# arduino_uno_pcb__with_lcd.net
KiCad netlist of a schematic drawn in EAGLE
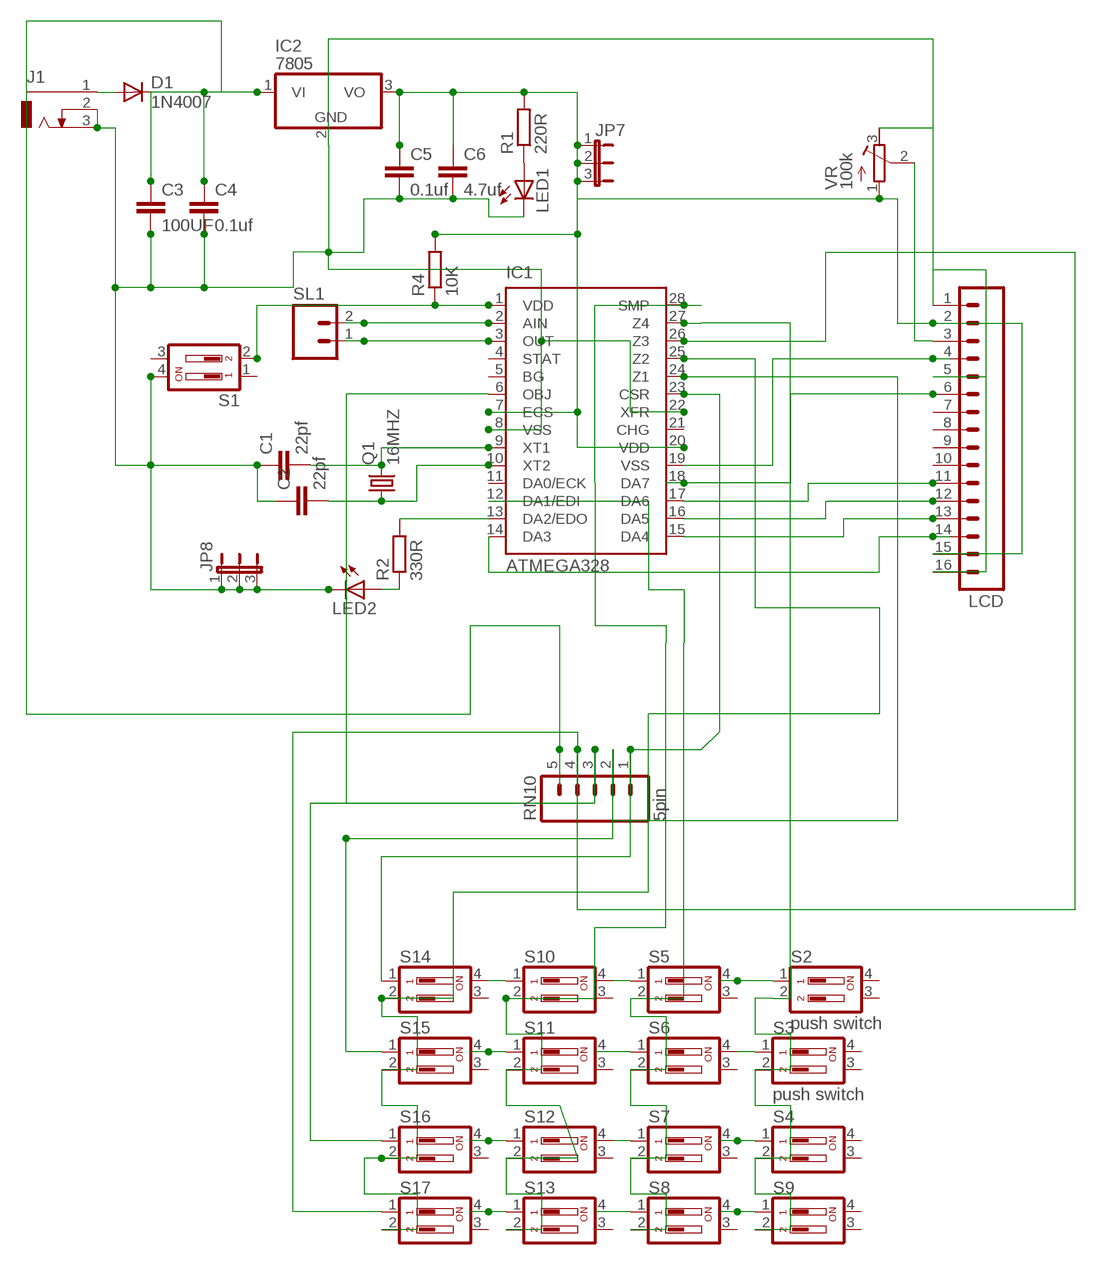
[diagram p0: schematic, sheet 1]

(export (version "E")
  (design (tool "Eeschema 10.0.6"))
  (components
    (comp (ref "C1")
      (value "22pf")
      (footprint "eagle-import:C2.5-2")
      (libsource (lib "eagle-import") (part "C2.5/2"))
    )
    (comp (ref "C2")
      (value "22pf")
      (footprint "eagle-import:C2.5-2")
      (libsource (lib "eagle-import") (part "C2.5/2"))
    )
    (comp (ref "C3")
      (value "100UF")
      (footprint "eagle-import:C2.5-2")
      (libsource (lib "eagle-import") (part "C2.5/2"))
    )
    (comp (ref "C4")
      (value "0.1uf")
      (footprint "eagle-import:C2.5-2")
      (libsource (lib "eagle-import") (part "C2.5/2"))
    )
    (comp (ref "C5")
      (value "0.1uf")
      (footprint "eagle-import:C2.5-2")
      (libsource (lib "eagle-import") (part "C2.5/2"))
    )
    (comp (ref "C6")
      (value "4.7uf")
      (footprint "eagle-import:C2.5-2")
      (libsource (lib "eagle-import") (part "C2.5/2"))
    )
    (comp (ref "D1")
      (value "1N4007")
      (footprint "eagle-import:DO41-10")
      (libsource (lib "eagle-import") (part "1N4004"))
    )
    (comp (ref "IC1")
      (value "ATMEGA328")
      (footprint "eagle-import:DIL28-3")
      (libsource (lib "eagle-import") (part "QT9701BD"))
    )
    (comp (ref "IC2")
      (value "7805")
      (footprint "eagle-import:TO220V")
      (libsource (lib "eagle-import") (part "78TV6"))
    )
    (comp (ref "J1")
      (value "DCJ0303")
      (footprint "eagle-import:DCJ0303")
      (libsource (lib "eagle-import") (part "DCJ0303"))
    )
    (comp (ref "JP7")
      (value "JP2E")
      (footprint "eagle-import:JP2")
      (libsource (lib "eagle-import") (part "JP2E"))
    )
    (comp (ref "JP8")
      (value "JP2E")
      (footprint "eagle-import:JP2")
      (libsource (lib "eagle-import") (part "JP2E"))
    )
    (comp (ref "LCD")
      (value "M16")
      (footprint "eagle-import:16P")
      (libsource (lib "eagle-import") (part "M16"))
    )
    (comp (ref "LED1")
      (value "LED3MM")
      (footprint "eagle-import:LED3MM")
      (libsource (lib "eagle-import") (part "LED3MM"))
    )
    (comp (ref "LED2")
      (value "LED3MM")
      (footprint "eagle-import:LED3MM")
      (libsource (lib "eagle-import") (part "LED3MM"))
    )
    (comp (ref "Q1")
      (value "16MHZ")
      (footprint "eagle-import:HC49_S")
      (libsource (lib "eagle-import") (part "CRYSTALHC49S"))
    )
    (comp (ref "R1")
      (value "220R")
      (footprint "eagle-import:0207_10")
      (libsource (lib "eagle-import") (part "R-EU_0207/10"))
    )
    (comp (ref "R2")
      (value "330R")
      (footprint "eagle-import:0207_10")
      (libsource (lib "eagle-import") (part "R-EU_0207/10"))
    )
    (comp (ref "R4")
      (value "10K")
      (footprint "eagle-import:0207_10")
      (libsource (lib "eagle-import") (part "R-EU_0207/10"))
    )
    (comp (ref "RN10")
      (value "5pin")
      (footprint "eagle-import:05P")
      (libsource (lib "eagle-import") (part "M05"))
    )
    (comp (ref "S1")
      (value "DP02")
      (footprint "eagle-import:DP-02")
      (fields (field (name "MPN") "MCDP02"))
      (libsource (lib "eagle-import") (part "DP02"))
    )
    (comp (ref "S2")
      (value "push switch")
      (footprint "eagle-import:DP-02")
      (fields (field (name "MPN") "MCDP02"))
      (libsource (lib "eagle-import") (part "DP02"))
    )
    (comp (ref "S3")
      (value "push switch")
      (footprint "eagle-import:DP-02")
      (fields (field (name "MPN") "MCDP02"))
      (libsource (lib "eagle-import") (part "DP02"))
    )
    (comp (ref "S4")
      (value "DP02")
      (footprint "eagle-import:DP-02")
      (fields (field (name "MPN") "MCDP02"))
      (libsource (lib "eagle-import") (part "DP02"))
    )
    (comp (ref "S5")
      (value "DP02")
      (footprint "eagle-import:DP-02")
      (fields (field (name "MPN") "MCDP02"))
      (libsource (lib "eagle-import") (part "DP02"))
    )
    (comp (ref "S6")
      (value "DP02")
      (footprint "eagle-import:DP-02")
      (fields (field (name "MPN") "MCDP02"))
      (libsource (lib "eagle-import") (part "DP02"))
    )
    (comp (ref "S7")
      (value "DP02")
      (footprint "eagle-import:DP-02")
      (fields (field (name "MPN") "MCDP02"))
      (libsource (lib "eagle-import") (part "DP02"))
    )
    (comp (ref "S8")
      (value "DP02")
      (footprint "eagle-import:DP-02")
      (fields (field (name "MPN") "MCDP02"))
      (libsource (lib "eagle-import") (part "DP02"))
    )
    (comp (ref "S9")
      (value "DP02")
      (footprint "eagle-import:DP-02")
      (fields (field (name "MPN") "MCDP02"))
      (libsource (lib "eagle-import") (part "DP02"))
    )
    (comp (ref "S10")
      (value "DP02")
      (footprint "eagle-import:DP-02")
      (fields (field (name "MPN") "MCDP02"))
      (libsource (lib "eagle-import") (part "DP02"))
    )
    (comp (ref "S11")
      (value "DP02")
      (footprint "eagle-import:DP-02")
      (fields (field (name "MPN") "MCDP02"))
      (libsource (lib "eagle-import") (part "DP02"))
    )
    (comp (ref "S12")
      (value "DP02")
      (footprint "eagle-import:DP-02")
      (fields (field (name "MPN") "MCDP02"))
      (libsource (lib "eagle-import") (part "DP02"))
    )
    (comp (ref "S13")
      (value "DP02")
      (footprint "eagle-import:DP-02")
      (fields (field (name "MPN") "MCDP02"))
      (libsource (lib "eagle-import") (part "DP02"))
    )
    (comp (ref "S14")
      (value "DP02")
      (footprint "eagle-import:DP-02")
      (fields (field (name "MPN") "MCDP02"))
      (libsource (lib "eagle-import") (part "DP02"))
    )
    (comp (ref "S15")
      (value "DP02")
      (footprint "eagle-import:DP-02")
      (fields (field (name "MPN") "MCDP02"))
      (libsource (lib "eagle-import") (part "DP02"))
    )
    (comp (ref "S16")
      (value "DP02")
      (footprint "eagle-import:DP-02")
      (fields (field (name "MPN") "MCDP02"))
      (libsource (lib "eagle-import") (part "DP02"))
    )
    (comp (ref "S17")
      (value "DP02")
      (footprint "eagle-import:DP-02")
      (fields (field (name "MPN") "MCDP02"))
      (libsource (lib "eagle-import") (part "DP02"))
    )
    (comp (ref "SL1")
      (value "M02")
      (footprint "eagle-import:02P")
      (libsource (lib "eagle-import") (part "M02"))
    )
    (comp (ref "VR")
      (value "100k")
      (footprint "eagle-import:RTRIM64P")
      (libsource (lib "eagle-import") (part "R-TRIMM64P"))
    )
  )
  (nets
    (net (code "1") (name "Net-(D1-PadA)") (class "Default")
      (node (ref "D1") (pin "A") (pinfunction "A_A") (pintype "passive"))
      (node (ref "J1") (pin "1") (pinfunction "1_1") (pintype "passive"))
    )
    (net (code "2") (name "Net-(IC1-AIN)") (class "Default")
      (node (ref "IC1") (pin "2") (pinfunction "AIN_2") (pintype "input"))
      (node (ref "SL1") (pin "2") (pinfunction "2_2") (pintype "passive"))
    )
    (net (code "3") (name "Net-(IC1-CSR)") (class "Default")
      (node (ref "IC1") (pin "23") (pinfunction "CSR_23") (pintype "output"))
      (node (ref "RN10") (pin "1") (pinfunction "1_1") (pintype "passive"))
      (node (ref "S14") (pin "1") (pinfunction "1_1") (pintype "passive"))
    )
    (net (code "4") (name "Net-(IC1-DA1{slash}EDI)") (class "Default")
      (node (ref "IC1") (pin "12") (pinfunction "DA1/EDI_12") (pintype "output"))
      (node (ref "S5") (pin "2") (pinfunction "2_2") (pintype "passive"))
      (node (ref "S6") (pin "2") (pinfunction "2_2") (pintype "passive"))
      (node (ref "S7") (pin "2") (pinfunction "2_2") (pintype "passive"))
      (node (ref "S8") (pin "2") (pinfunction "2_2") (pintype "passive"))
    )
    (net (code "5") (name "Net-(IC1-DA2{slash}EDO)") (class "Default")
      (node (ref "IC1") (pin "13") (pinfunction "DA2/EDO_13") (pintype "output"))
      (node (ref "R2") (pin "2") (pinfunction "2_2") (pintype "passive"))
    )
    (net (code "6") (name "Net-(IC1-DA3)") (class "Default")
      (node (ref "IC1") (pin "14") (pinfunction "DA3_14") (pintype "output"))
      (node (ref "LCD") (pin "14") (pinfunction "14_14") (pintype "passive"))
    )
    (net (code "7") (name "Net-(IC1-DA4)") (class "Default")
      (node (ref "IC1") (pin "15") (pinfunction "DA4_15") (pintype "output"))
      (node (ref "LCD") (pin "13") (pinfunction "13_13") (pintype "passive"))
    )
    (net (code "8") (name "Net-(IC1-DA5)") (class "Default")
      (node (ref "IC1") (pin "16") (pinfunction "DA5_16") (pintype "output"))
      (node (ref "LCD") (pin "12") (pinfunction "12_12") (pintype "passive"))
    )
    (net (code "9") (name "Net-(IC1-DA6)") (class "Default")
      (node (ref "IC1") (pin "17") (pinfunction "DA6_17") (pintype "output"))
      (node (ref "LCD") (pin "11") (pinfunction "11_11") (pintype "passive"))
    )
    (net (code "10") (name "Net-(IC1-DA7)") (class "Default")
      (node (ref "IC1") (pin "18") (pinfunction "DA7_18") (pintype "output"))
      (node (ref "LCD") (pin "6") (pinfunction "6_6") (pintype "passive"))
    )
    (net (code "11") (name "Net-(IC1-ECS)") (class "Default")
      (node (ref "C5") (pin "1") (pinfunction "1_1") (pintype "passive"))
      (node (ref "C6") (pin "1") (pinfunction "1_1") (pintype "passive"))
      (node (ref "IC1") (pin "20") (pinfunction "VDD_20") (pintype "input"))
      (node (ref "IC1") (pin "7") (pinfunction "ECS_7") (pintype "output"))
      (node (ref "IC2") (pin "3") (pinfunction "VO_3") (pintype "passive"))
      (node (ref "JP7") (pin "1") (pinfunction "1_1") (pintype "passive"))
      (node (ref "JP7") (pin "2") (pinfunction "2_2") (pintype "passive"))
      (node (ref "JP7") (pin "3") (pinfunction "3_3") (pintype "passive"))
      (node (ref "LCD") (pin "15") (pinfunction "15_15") (pintype "passive"))
      (node (ref "LCD") (pin "2") (pinfunction "2_2") (pintype "passive"))
      (node (ref "R1") (pin "2") (pinfunction "2_2") (pintype "passive"))
      (node (ref "R4") (pin "2") (pinfunction "2_2") (pintype "passive"))
      (node (ref "VR") (pin "1") (pinfunction "E_1") (pintype "passive"))
    )
    (net (code "12") (name "Net-(IC1-OBJ)") (class "Default")
      (node (ref "IC1") (pin "6") (pinfunction "OBJ_6") (pintype "input"))
      (node (ref "RN10") (pin "3") (pinfunction "3_3") (pintype "passive"))
      (node (ref "S16") (pin "1") (pinfunction "1_1") (pintype "passive"))
    )
    (net (code "13") (name "Net-(IC1-OUT)") (class "Default")
      (node (ref "IC1") (pin "3") (pinfunction "OUT_3") (pintype "output"))
      (node (ref "SL1") (pin "1") (pinfunction "1_1") (pintype "passive"))
    )
    (net (code "14") (name "Net-(IC1-SMP)") (class "Default")
      (node (ref "IC1") (pin "28") (pinfunction "SMP_28") (pintype "output"))
      (node (ref "S10") (pin "2") (pinfunction "2_2") (pintype "passive"))
      (node (ref "S11") (pin "2") (pinfunction "2_2") (pintype "passive"))
      (node (ref "S12") (pin "2") (pinfunction "2_2") (pintype "passive"))
      (node (ref "S13") (pin "2") (pinfunction "2_2") (pintype "passive"))
    )
    (net (code "15") (name "Net-(IC1-VDD-Pad1)") (class "Default")
      (node (ref "IC1") (pin "1") (pinfunction "VDD_1") (pintype "input"))
      (node (ref "R4") (pin "1") (pinfunction "1_1") (pintype "passive"))
      (node (ref "S1") (pin "2") (pinfunction "2_2") (pintype "passive"))
    )
    (net (code "16") (name "Net-(IC1-VSS-Pad19)") (class "Default")
      (node (ref "IC1") (pin "19") (pinfunction "VSS_19") (pintype "input"))
      (node (ref "LCD") (pin "4") (pinfunction "4_4") (pintype "passive"))
    )
    (net (code "17") (name "Net-(IC1-XFR)") (class "Default")
      (node (ref "C1") (pin "1") (pinfunction "1_1") (pintype "passive"))
      (node (ref "C2") (pin "1") (pinfunction "1_1") (pintype "passive"))
      (node (ref "C3") (pin "2") (pinfunction "2_2") (pintype "passive"))
      (node (ref "C4") (pin "2") (pinfunction "2_2") (pintype "passive"))
      (node (ref "C5") (pin "2") (pinfunction "2_2") (pintype "passive"))
      (node (ref "C6") (pin "2") (pinfunction "2_2") (pintype "passive"))
      (node (ref "IC1") (pin "22") (pinfunction "XFR_22") (pintype "output"))
      (node (ref "IC1") (pin "8") (pinfunction "VSS_8") (pintype "input"))
      (node (ref "IC2") (pin "2") (pinfunction "GND_2") (pintype "passive"))
      (node (ref "J1") (pin "2") (pinfunction "2_2") (pintype "passive"))
      (node (ref "J1") (pin "3") (pinfunction "3_3") (pintype "passive"))
      (node (ref "JP8") (pin "1") (pinfunction "1_1") (pintype "passive"))
      (node (ref "JP8") (pin "2") (pinfunction "2_2") (pintype "passive"))
      (node (ref "JP8") (pin "3") (pinfunction "3_3") (pintype "passive"))
      (node (ref "LCD") (pin "1") (pinfunction "1_1") (pintype "passive"))
      (node (ref "LCD") (pin "16") (pinfunction "16_16") (pintype "passive"))
      (node (ref "LCD") (pin "5") (pinfunction "5_5") (pintype "passive"))
      (node (ref "LED1") (pin "K") (pinfunction "C_K") (pintype "passive"))
      (node (ref "LED2") (pin "K") (pinfunction "C_K") (pintype "passive"))
      (node (ref "S1") (pin "4") (pinfunction "4_4") (pintype "passive"))
      (node (ref "VR") (pin "3") (pinfunction "A_3") (pintype "passive"))
    )
    (net (code "18") (name "Net-(IC1-XT1)") (class "Default")
      (node (ref "C1") (pin "2") (pinfunction "2_2") (pintype "passive"))
      (node (ref "IC1") (pin "9") (pinfunction "XT1_9") (pintype "input"))
      (node (ref "Q1") (pin "2") (pinfunction "2_2") (pintype "passive"))
    )
    (net (code "19") (name "Net-(IC1-XT2)") (class "Default")
      (node (ref "C2") (pin "2") (pinfunction "2_2") (pintype "passive"))
      (node (ref "IC1") (pin "10") (pinfunction "XT2_10") (pintype "output"))
      (node (ref "Q1") (pin "1") (pinfunction "1_1") (pintype "passive"))
    )
    (net (code "20") (name "Net-(IC1-Z1)") (class "Default")
      (node (ref "IC1") (pin "24") (pinfunction "Z1_24") (pintype "output"))
      (node (ref "RN10") (pin "2") (pinfunction "2_2") (pintype "passive"))
      (node (ref "S15") (pin "1") (pinfunction "1_1") (pintype "passive"))
    )
    (net (code "21") (name "Net-(IC1-Z2)") (class "Default")
      (node (ref "IC1") (pin "25") (pinfunction "Z2_25") (pintype "output"))
      (node (ref "S14") (pin "2") (pinfunction "2_2") (pintype "passive"))
      (node (ref "S15") (pin "2") (pinfunction "2_2") (pintype "passive"))
      (node (ref "S16") (pin "2") (pinfunction "2_2") (pintype "passive"))
      (node (ref "S17") (pin "2") (pinfunction "2_2") (pintype "passive"))
    )
    (net (code "22") (name "Net-(IC1-Z3)") (class "Default")
      (node (ref "IC1") (pin "26") (pinfunction "Z3_26") (pintype "output"))
      (node (ref "RN10") (pin "4") (pinfunction "4_4") (pintype "passive"))
      (node (ref "S17") (pin "1") (pinfunction "1_1") (pintype "passive"))
    )
    (net (code "23") (name "Net-(IC1-Z4)") (class "Default")
      (node (ref "IC1") (pin "27") (pinfunction "Z4_27") (pintype "output"))
      (node (ref "S2") (pin "2") (pinfunction "2_2") (pintype "passive"))
      (node (ref "S3") (pin "2") (pinfunction "2_2") (pintype "passive"))
      (node (ref "S4") (pin "2") (pinfunction "2_2") (pintype "passive"))
      (node (ref "S9") (pin "2") (pinfunction "2_2") (pintype "passive"))
    )
    (net (code "24") (name "Net-(IC2-VI)") (class "Default")
      (node (ref "C3") (pin "1") (pinfunction "1_1") (pintype "passive"))
      (node (ref "C4") (pin "1") (pinfunction "1_1") (pintype "passive"))
      (node (ref "D1") (pin "C") (pinfunction "C_C") (pintype "passive"))
      (node (ref "IC2") (pin "1") (pinfunction "VI_1") (pintype "input"))
      (node (ref "RN10") (pin "5") (pinfunction "5_5") (pintype "passive"))
    )
    (net (code "25") (name "Net-(LED1-PadA)") (class "Default")
      (node (ref "LED1") (pin "A") (pinfunction "A_A") (pintype "passive"))
      (node (ref "R1") (pin "1") (pinfunction "1_1") (pintype "passive"))
    )
    (net (code "26") (name "Net-(LED2-PadA)") (class "Default")
      (node (ref "LED2") (pin "A") (pinfunction "A_A") (pintype "passive"))
      (node (ref "R2") (pin "1") (pinfunction "1_1") (pintype "passive"))
    )
    (net (code "27") (name "Net-(S2-Pad1)") (class "Default")
      (node (ref "S2") (pin "1") (pinfunction "1_1") (pintype "passive"))
      (node (ref "S5") (pin "4") (pinfunction "4_4") (pintype "passive"))
    )
    (net (code "28") (name "Net-(S3-Pad1)") (class "Default")
      (node (ref "S3") (pin "1") (pinfunction "1_1") (pintype "passive"))
      (node (ref "S6") (pin "4") (pinfunction "4_4") (pintype "passive"))
    )
    (net (code "29") (name "Net-(S4-Pad1)") (class "Default")
      (node (ref "S4") (pin "1") (pinfunction "1_1") (pintype "passive"))
      (node (ref "S7") (pin "4") (pinfunction "4_4") (pintype "passive"))
    )
    (net (code "30") (name "Net-(S8-Pad4)") (class "Default")
      (node (ref "S8") (pin "4") (pinfunction "4_4") (pintype "passive"))
      (node (ref "S9") (pin "1") (pinfunction "1_1") (pintype "passive"))
    )
    (net (code "31") (name "Net-(S10-Pad1)") (class "Default")
      (node (ref "S10") (pin "1") (pinfunction "1_1") (pintype "passive"))
      (node (ref "S14") (pin "4") (pinfunction "4_4") (pintype "passive"))
    )
    (net (code "32") (name "Net-(S10-Pad4)") (class "Default")
      (node (ref "S10") (pin "4") (pinfunction "4_4") (pintype "passive"))
      (node (ref "S5") (pin "1") (pinfunction "1_1") (pintype "passive"))
    )
    (net (code "33") (name "Net-(S11-Pad1)") (class "Default")
      (node (ref "S11") (pin "1") (pinfunction "1_1") (pintype "passive"))
      (node (ref "S15") (pin "4") (pinfunction "4_4") (pintype "passive"))
    )
    (net (code "34") (name "Net-(S11-Pad4)") (class "Default")
      (node (ref "S11") (pin "4") (pinfunction "4_4") (pintype "passive"))
      (node (ref "S6") (pin "1") (pinfunction "1_1") (pintype "passive"))
    )
    (net (code "35") (name "Net-(S12-Pad1)") (class "Default")
      (node (ref "S12") (pin "1") (pinfunction "1_1") (pintype "passive"))
      (node (ref "S16") (pin "4") (pinfunction "4_4") (pintype "passive"))
    )
    (net (code "36") (name "Net-(S12-Pad4)") (class "Default")
      (node (ref "S12") (pin "4") (pinfunction "4_4") (pintype "passive"))
      (node (ref "S7") (pin "1") (pinfunction "1_1") (pintype "passive"))
    )
    (net (code "37") (name "Net-(S13-Pad1)") (class "Default")
      (node (ref "S13") (pin "1") (pinfunction "1_1") (pintype "passive"))
      (node (ref "S17") (pin "4") (pinfunction "4_4") (pintype "passive"))
    )
    (net (code "38") (name "Net-(S13-Pad4)") (class "Default")
      (node (ref "S13") (pin "4") (pinfunction "4_4") (pintype "passive"))
      (node (ref "S8") (pin "1") (pinfunction "1_1") (pintype "passive"))
    )
    (net (code "39") (name "Net-(VR-S)") (class "Default")
      (node (ref "LCD") (pin "3") (pinfunction "3_3") (pintype "passive"))
      (node (ref "VR") (pin "2") (pinfunction "S_2") (pintype "passive"))
    )
    (net (code "40") (name "unconnected-(IC1-BG-Pad5)") (class "Default")
      (node (ref "IC1") (pin "5") (pinfunction "BG_5") (pintype "input"))
    )
    (net (code "41") (name "unconnected-(IC1-CHG-Pad21)") (class "Default")
      (node (ref "IC1") (pin "21") (pinfunction "CHG_21") (pintype "output"))
    )
    (net (code "42") (name "unconnected-(IC1-DA0{slash}ECK-Pad11)") (class "Default")
      (node (ref "IC1") (pin "11") (pinfunction "DA0/ECK_11") (pintype "output"))
    )
    (net (code "43") (name "unconnected-(IC1-STAT-Pad4)") (class "Default")
      (node (ref "IC1") (pin "4") (pinfunction "STAT_4") (pintype "output"))
    )
    (net (code "44") (name "unconnected-(LCD-Pad7)") (class "Default")
      (node (ref "LCD") (pin "7") (pinfunction "7_7") (pintype "passive"))
    )
    (net (code "45") (name "unconnected-(LCD-Pad8)") (class "Default")
      (node (ref "LCD") (pin "8") (pinfunction "8_8") (pintype "passive"))
    )
    (net (code "46") (name "unconnected-(LCD-Pad9)") (class "Default")
      (node (ref "LCD") (pin "9") (pinfunction "9_9") (pintype "passive"))
    )
    (net (code "47") (name "unconnected-(LCD-Pad10)") (class "Default")
      (node (ref "LCD") (pin "10") (pinfunction "10_10") (pintype "passive"))
    )
    (net (code "48") (name "unconnected-(S1-Pad1)") (class "Default")
      (node (ref "S1") (pin "1") (pinfunction "1_1") (pintype "passive"))
    )
    (net (code "49") (name "unconnected-(S1-Pad3)") (class "Default")
      (node (ref "S1") (pin "3") (pinfunction "3_3") (pintype "passive"))
    )
    (net (code "50") (name "unconnected-(S2-Pad3)") (class "Default")
      (node (ref "S2") (pin "3") (pinfunction "3_3") (pintype "passive"))
    )
    (net (code "51") (name "unconnected-(S2-Pad4)") (class "Default")
      (node (ref "S2") (pin "4") (pinfunction "4_4") (pintype "passive"))
    )
    (net (code "52") (name "unconnected-(S3-Pad3)") (class "Default")
      (node (ref "S3") (pin "3") (pinfunction "3_3") (pintype "passive"))
    )
    (net (code "53") (name "unconnected-(S3-Pad4)") (class "Default")
      (node (ref "S3") (pin "4") (pinfunction "4_4") (pintype "passive"))
    )
    (net (code "54") (name "unconnected-(S4-Pad3)") (class "Default")
      (node (ref "S4") (pin "3") (pinfunction "3_3") (pintype "passive"))
    )
    (net (code "55") (name "unconnected-(S4-Pad4)") (class "Default")
      (node (ref "S4") (pin "4") (pinfunction "4_4") (pintype "passive"))
    )
    (net (code "56") (name "unconnected-(S5-Pad3)") (class "Default")
      (node (ref "S5") (pin "3") (pinfunction "3_3") (pintype "passive"))
    )
    (net (code "57") (name "unconnected-(S6-Pad3)") (class "Default")
      (node (ref "S6") (pin "3") (pinfunction "3_3") (pintype "passive"))
    )
    (net (code "58") (name "unconnected-(S7-Pad3)") (class "Default")
      (node (ref "S7") (pin "3") (pinfunction "3_3") (pintype "passive"))
    )
    (net (code "59") (name "unconnected-(S8-Pad3)") (class "Default")
      (node (ref "S8") (pin "3") (pinfunction "3_3") (pintype "passive"))
    )
    (net (code "60") (name "unconnected-(S9-Pad3)") (class "Default")
      (node (ref "S9") (pin "3") (pinfunction "3_3") (pintype "passive"))
    )
    (net (code "61") (name "unconnected-(S9-Pad4)") (class "Default")
      (node (ref "S9") (pin "4") (pinfunction "4_4") (pintype "passive"))
    )
    (net (code "62") (name "unconnected-(S10-Pad3)") (class "Default")
      (node (ref "S10") (pin "3") (pinfunction "3_3") (pintype "passive"))
    )
    (net (code "63") (name "unconnected-(S11-Pad3)") (class "Default")
      (node (ref "S11") (pin "3") (pinfunction "3_3") (pintype "passive"))
    )
    (net (code "64") (name "unconnected-(S12-Pad3)") (class "Default")
      (node (ref "S12") (pin "3") (pinfunction "3_3") (pintype "passive"))
    )
    (net (code "65") (name "unconnected-(S13-Pad3)") (class "Default")
      (node (ref "S13") (pin "3") (pinfunction "3_3") (pintype "passive"))
    )
    (net (code "66") (name "unconnected-(S14-Pad3)") (class "Default")
      (node (ref "S14") (pin "3") (pinfunction "3_3") (pintype "passive"))
    )
    (net (code "67") (name "unconnected-(S15-Pad3)") (class "Default")
      (node (ref "S15") (pin "3") (pinfunction "3_3") (pintype "passive"))
    )
    (net (code "68") (name "unconnected-(S16-Pad3)") (class "Default")
      (node (ref "S16") (pin "3") (pinfunction "3_3") (pintype "passive"))
    )
    (net (code "69") (name "unconnected-(S17-Pad3)") (class "Default")
      (node (ref "S17") (pin "3") (pinfunction "3_3") (pintype "passive"))
    )
  )
)
